# LRT1919.net
KiCad netlist of a schematic drawn in EAGLE
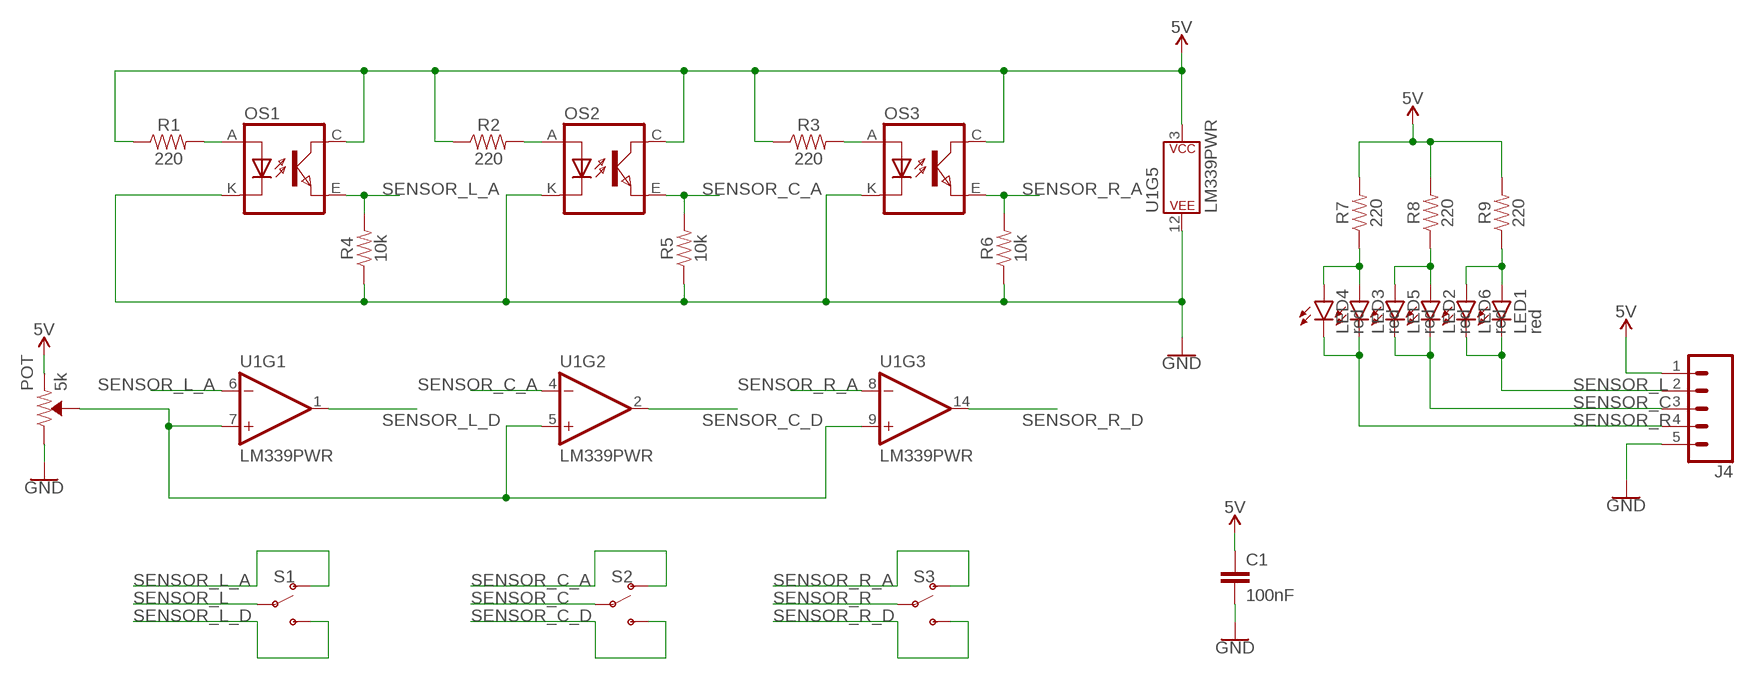
[diagram p0: schematic, sheet 1]

(export (version "E")
  (design (tool "Eeschema 10.0.6"))
  (components
    (comp (ref "C1")
      (value "100nF")
      (footprint "eagle-import:0805")
      (libsource (lib "eagle-import") (part "0.33UF/330NF-0805-50V-10%"))
    )
    (comp (ref "J4")
      (value "CONN_05")
      (footprint "eagle-import:1X05")
      (libsource (lib "eagle-import") (part "CONN_05"))
    )
    (comp (ref "LED1")
      (value "red")
      (footprint "eagle-import:SML0805")
      (libsource (lib "eagle-import") (part "LEDSML0805"))
    )
    (comp (ref "LED2")
      (value "red")
      (footprint "eagle-import:SML0805")
      (libsource (lib "eagle-import") (part "LEDSML0805"))
    )
    (comp (ref "LED3")
      (value "red")
      (footprint "eagle-import:SML0805")
      (libsource (lib "eagle-import") (part "LEDSML0805"))
    )
    (comp (ref "LED4")
      (value "red")
      (footprint "eagle-import:SML0805")
      (libsource (lib "eagle-import") (part "LEDSML0805"))
    )
    (comp (ref "LED5")
      (value "red")
      (footprint "eagle-import:SML0805")
      (libsource (lib "eagle-import") (part "LEDSML0805"))
    )
    (comp (ref "LED6")
      (value "red")
      (footprint "eagle-import:SML0805")
      (libsource (lib "eagle-import") (part "LEDSML0805"))
    )
    (comp (ref "OS1")
      (value "TCRT5000")
      (footprint "eagle-import:TCRT5000")
      (libsource (lib "eagle-import") (part "TCRT5000"))
    )
    (comp (ref "OS2")
      (value "TCRT5000")
      (footprint "eagle-import:TCRT5000")
      (libsource (lib "eagle-import") (part "TCRT5000"))
    )
    (comp (ref "OS3")
      (value "TCRT5000")
      (footprint "eagle-import:TCRT5000")
      (libsource (lib "eagle-import") (part "TCRT5000"))
    )
    (comp (ref "POT")
      (value "5k")
      (footprint "eagle-import:TRIMPOT-SMD-5MM")
      (libsource (lib "eagle-import") (part "TRIMPOT-SMD-5MM-CLOSED-1/4W-20%"))
    )
    (comp (ref "R1")
      (value "220")
      (footprint "eagle-import:0805")
      (libsource (lib "eagle-import") (part "0.22OHM-0805-1/4W-1%"))
    )
    (comp (ref "R2")
      (value "220")
      (footprint "eagle-import:0805")
      (libsource (lib "eagle-import") (part "0.22OHM-0805-1/4W-1%"))
    )
    (comp (ref "R3")
      (value "220")
      (footprint "eagle-import:0805")
      (libsource (lib "eagle-import") (part "0.22OHM-0805-1/4W-1%"))
    )
    (comp (ref "R4")
      (value "10k")
      (footprint "eagle-import:0805")
      (libsource (lib "eagle-import") (part "0.22OHM-0805-1/4W-1%"))
    )
    (comp (ref "R5")
      (value "10k")
      (footprint "eagle-import:0805")
      (libsource (lib "eagle-import") (part "0.22OHM-0805-1/4W-1%"))
    )
    (comp (ref "R6")
      (value "10k")
      (footprint "eagle-import:0805")
      (libsource (lib "eagle-import") (part "0.22OHM-0805-1/4W-1%"))
    )
    (comp (ref "R7")
      (value "220")
      (footprint "eagle-import:0805")
      (libsource (lib "eagle-import") (part "0.22OHM-0805-1/4W-1%"))
    )
    (comp (ref "R8")
      (value "220")
      (footprint "eagle-import:0805")
      (libsource (lib "eagle-import") (part "0.22OHM-0805-1/4W-1%"))
    )
    (comp (ref "R9")
      (value "220")
      (footprint "eagle-import:0805")
      (libsource (lib "eagle-import") (part "0.22OHM-0805-1/4W-1%"))
    )
    (comp (ref "S1")
      (value "SWITCH-SPDT-SMD-RIGHT-ANGLE")
      (footprint "eagle-import:SWITCH_SPST_SMD_A")
      (libsource (lib "eagle-import") (part "SWITCH-SPDT-SMD-RIGHT-ANGLE"))
    )
    (comp (ref "S2")
      (value "SWITCH-SPDT-SMD-RIGHT-ANGLE")
      (footprint "eagle-import:SWITCH_SPST_SMD_A")
      (libsource (lib "eagle-import") (part "SWITCH-SPDT-SMD-RIGHT-ANGLE"))
    )
    (comp (ref "S3")
      (value "SWITCH-SPDT-SMD-RIGHT-ANGLE")
      (footprint "eagle-import:SWITCH_SPST_SMD_A")
      (libsource (lib "eagle-import") (part "SWITCH-SPDT-SMD-RIGHT-ANGLE"))
    )
    (comp (ref "U1")
      (value "LM339PWR")
      (footprint "eagle-import:TSSOP-14")
      (libsource (lib "eagle-import") (part "LM339"))
    )
  )
  (nets
    (net (code "1") (name "/SENSOR_C") (class "Default")
      (node (ref "J4") (pin "3") (pinfunction "3_3") (pintype "passive"))
      (node (ref "LED2") (pin "C") (pinfunction "C_C") (pintype "passive"))
      (node (ref "LED5") (pin "C") (pinfunction "C_C") (pintype "passive"))
      (node (ref "S2") (pin "2") (pinfunction "P_2") (pintype "passive"))
    )
    (net (code "2") (name "/SENSOR_C_A") (class "Default")
      (node (ref "OS2") (pin "E") (pinfunction "EMITTER_E") (pintype "passive"))
      (node (ref "R5") (pin "2") (pinfunction "2_2") (pintype "passive"))
      (node (ref "S2") (pin "1") (pinfunction "O_1") (pintype "passive"))
      (node (ref "U1") (pin "4") (pinfunction "-IN_4") (pintype "input"))
    )
    (net (code "3") (name "/SENSOR_C_D") (class "Default")
      (node (ref "S2") (pin "3") (pinfunction "S_3") (pintype "passive"))
      (node (ref "U1") (pin "2") (pinfunction "OUT_2") (pintype "output"))
    )
    (net (code "4") (name "/SENSOR_L") (class "Default")
      (node (ref "J4") (pin "2") (pinfunction "2_2") (pintype "passive"))
      (node (ref "LED1") (pin "C") (pinfunction "C_C") (pintype "passive"))
      (node (ref "LED6") (pin "C") (pinfunction "C_C") (pintype "passive"))
      (node (ref "S1") (pin "2") (pinfunction "P_2") (pintype "passive"))
    )
    (net (code "5") (name "/SENSOR_L_A") (class "Default")
      (node (ref "OS1") (pin "E") (pinfunction "EMITTER_E") (pintype "passive"))
      (node (ref "R4") (pin "2") (pinfunction "2_2") (pintype "passive"))
      (node (ref "S1") (pin "1") (pinfunction "O_1") (pintype "passive"))
      (node (ref "U1") (pin "6") (pinfunction "-IN_6") (pintype "input"))
    )
    (net (code "6") (name "/SENSOR_L_D") (class "Default")
      (node (ref "S1") (pin "3") (pinfunction "S_3") (pintype "passive"))
      (node (ref "U1") (pin "1") (pinfunction "OUT_1") (pintype "output"))
    )
    (net (code "7") (name "/SENSOR_R") (class "Default")
      (node (ref "J4") (pin "4") (pinfunction "4_4") (pintype "passive"))
      (node (ref "LED3") (pin "C") (pinfunction "C_C") (pintype "passive"))
      (node (ref "LED4") (pin "C") (pinfunction "C_C") (pintype "passive"))
      (node (ref "S3") (pin "2") (pinfunction "P_2") (pintype "passive"))
    )
    (net (code "8") (name "/SENSOR_R_A") (class "Default")
      (node (ref "OS3") (pin "E") (pinfunction "EMITTER_E") (pintype "passive"))
      (node (ref "R6") (pin "2") (pinfunction "2_2") (pintype "passive"))
      (node (ref "S3") (pin "1") (pinfunction "O_1") (pintype "passive"))
      (node (ref "U1") (pin "8") (pinfunction "-IN_8") (pintype "input"))
    )
    (net (code "9") (name "/SENSOR_R_D") (class "Default")
      (node (ref "S3") (pin "3") (pinfunction "S_3") (pintype "passive"))
      (node (ref "U1") (pin "14") (pinfunction "OUT_14") (pintype "output"))
    )
    (net (code "10") (name "5V") (class "Default")
      (node (ref "C1") (pin "1") (pinfunction "1_1") (pintype "passive"))
      (node (ref "J4") (pin "1") (pinfunction "1_1") (pintype "passive"))
      (node (ref "OS1") (pin "C") (pinfunction "COLLECTOR_C") (pintype "passive"))
      (node (ref "OS2") (pin "C") (pinfunction "COLLECTOR_C") (pintype "passive"))
      (node (ref "OS3") (pin "C") (pinfunction "COLLECTOR_C") (pintype "passive"))
      (node (ref "POT") (pin "A") (pinfunction "CCW_A") (pintype "passive"))
      (node (ref "R1") (pin "1") (pinfunction "1_1") (pintype "passive"))
      (node (ref "R2") (pin "1") (pinfunction "1_1") (pintype "passive"))
      (node (ref "R3") (pin "1") (pinfunction "1_1") (pintype "passive"))
      (node (ref "R7") (pin "2") (pinfunction "2_2") (pintype "passive"))
      (node (ref "R8") (pin "2") (pinfunction "2_2") (pintype "passive"))
      (node (ref "R9") (pin "2") (pinfunction "2_2") (pintype "passive"))
      (node (ref "U1") (pin "3") (pinfunction "P$V+_3") (pintype "bidirectional"))
    )
    (net (code "11") (name "GND") (class "Default")
      (node (ref "C1") (pin "2") (pinfunction "2_2") (pintype "passive"))
      (node (ref "J4") (pin "5") (pinfunction "5_5") (pintype "passive"))
      (node (ref "OS1") (pin "K") (pinfunction "CATHODE_K") (pintype "passive"))
      (node (ref "OS2") (pin "K") (pinfunction "CATHODE_K") (pintype "passive"))
      (node (ref "OS3") (pin "K") (pinfunction "CATHODE_K") (pintype "passive"))
      (node (ref "POT") (pin "C") (pinfunction "CW_C") (pintype "passive"))
      (node (ref "R4") (pin "1") (pinfunction "1_1") (pintype "passive"))
      (node (ref "R5") (pin "1") (pinfunction "1_1") (pintype "passive"))
      (node (ref "R6") (pin "1") (pinfunction "1_1") (pintype "passive"))
      (node (ref "U1") (pin "12") (pinfunction "P$V-_12") (pintype "bidirectional"))
    )
    (net (code "12") (name "Net-(LED1-PadA)") (class "Default")
      (node (ref "LED1") (pin "A") (pinfunction "A_A") (pintype "passive"))
      (node (ref "LED6") (pin "A") (pinfunction "A_A") (pintype "passive"))
      (node (ref "R9") (pin "1") (pinfunction "1_1") (pintype "passive"))
    )
    (net (code "13") (name "Net-(LED2-PadA)") (class "Default")
      (node (ref "LED2") (pin "A") (pinfunction "A_A") (pintype "passive"))
      (node (ref "LED5") (pin "A") (pinfunction "A_A") (pintype "passive"))
      (node (ref "R8") (pin "1") (pinfunction "1_1") (pintype "passive"))
    )
    (net (code "14") (name "Net-(LED3-PadA)") (class "Default")
      (node (ref "LED3") (pin "A") (pinfunction "A_A") (pintype "passive"))
      (node (ref "LED4") (pin "A") (pinfunction "A_A") (pintype "passive"))
      (node (ref "R7") (pin "1") (pinfunction "1_1") (pintype "passive"))
    )
    (net (code "15") (name "Net-(OS1-ANODE)") (class "Default")
      (node (ref "OS1") (pin "A") (pinfunction "ANODE_A") (pintype "passive"))
      (node (ref "R1") (pin "2") (pinfunction "2_2") (pintype "passive"))
    )
    (net (code "16") (name "Net-(OS2-ANODE)") (class "Default")
      (node (ref "OS2") (pin "A") (pinfunction "ANODE_A") (pintype "passive"))
      (node (ref "R2") (pin "2") (pinfunction "2_2") (pintype "passive"))
    )
    (net (code "17") (name "Net-(OS3-ANODE)") (class "Default")
      (node (ref "OS3") (pin "A") (pinfunction "ANODE_A") (pintype "passive"))
      (node (ref "R3") (pin "2") (pinfunction "2_2") (pintype "passive"))
    )
    (net (code "18") (name "Net-(POT-WIPER)") (class "Default")
      (node (ref "POT") (pin "B") (pinfunction "WIPER_B") (pintype "passive"))
      (node (ref "U1") (pin "5") (pinfunction "+IN_5") (pintype "input"))
      (node (ref "U1") (pin "7") (pinfunction "+IN_7") (pintype "input"))
      (node (ref "U1") (pin "9") (pinfunction "+IN_9") (pintype "input"))
    )
  )
)
